# 06_RTL8711.net
KiCad netlist of a schematic drawn in Altium Designer
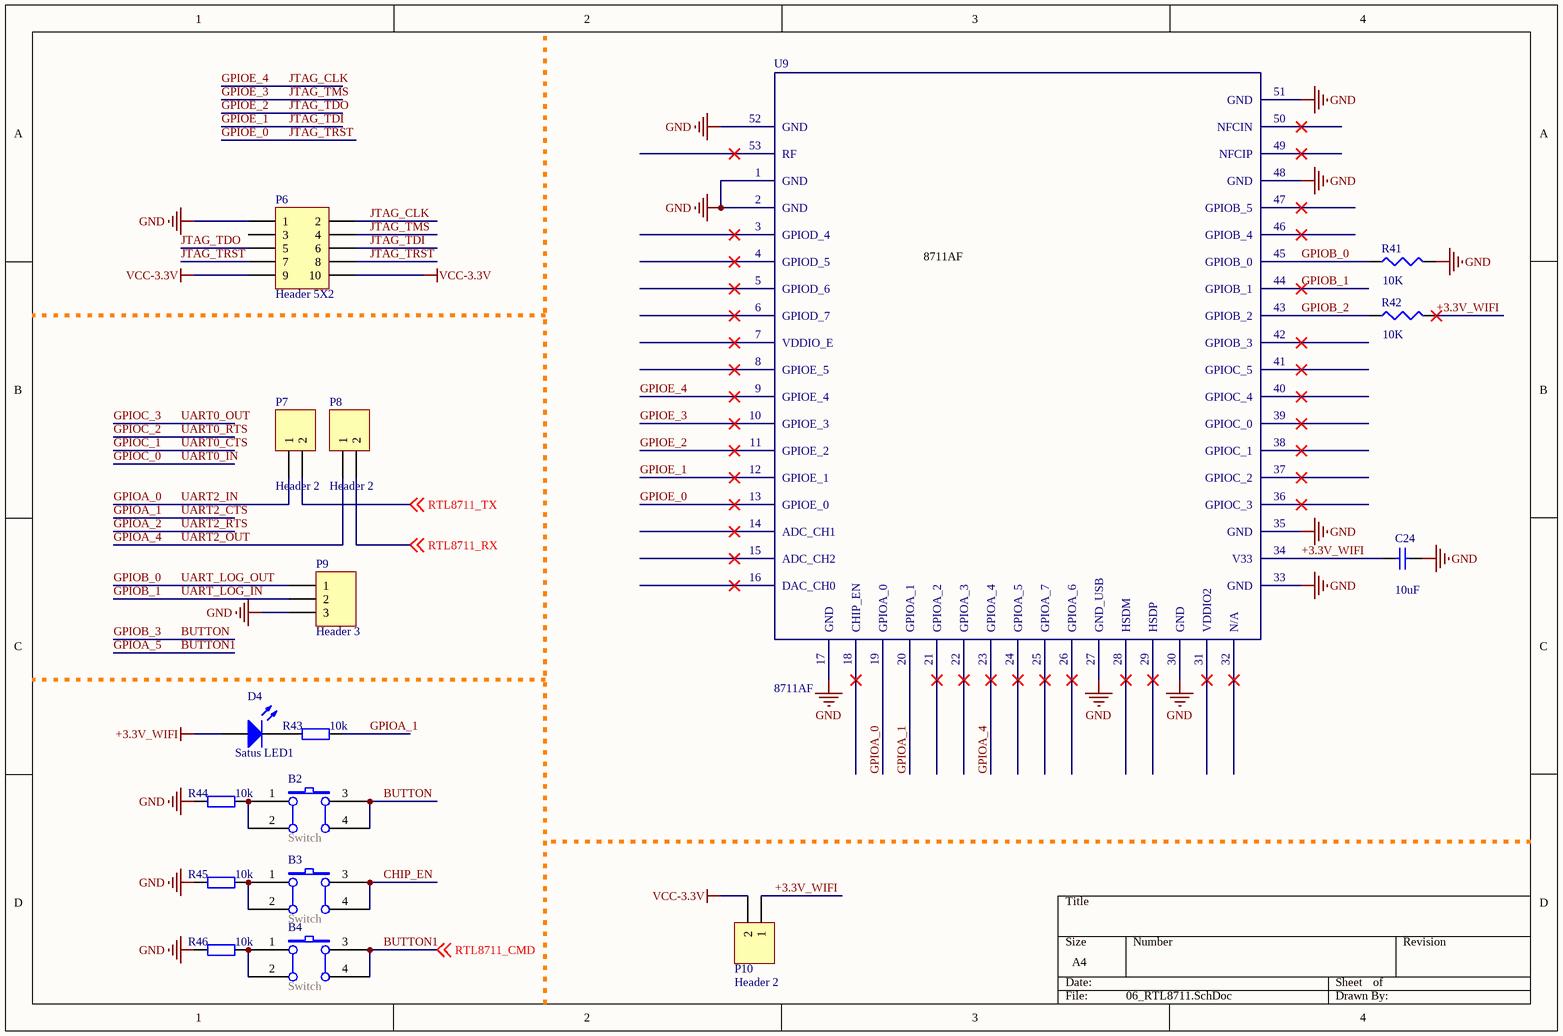
[diagram p0: 06_RTL8711.SchDoc]

(export (version "E")
  (design (tool "Eeschema 10.0.6"))
  (components
    (comp (ref "B2")
      (value "Switch")
      (footprint "Miscellaneous Modules:SWITCH-0.65/0.45")
      (description "Tactile Switch")
      (libsource (lib "Miscellaneous Modules") (part "Switch"))
    )
    (comp (ref "B3")
      (value "Switch")
      (footprint "Miscellaneous Modules:SWITCH-0.65/0.45")
      (description "Tactile Switch")
      (libsource (lib "Miscellaneous Modules") (part "Switch"))
    )
    (comp (ref "B4")
      (value "Switch")
      (footprint "Miscellaneous Modules:SWITCH-0.65/0.45")
      (description "Tactile Switch")
      (libsource (lib "Miscellaneous Modules") (part "Switch"))
    )
    (comp (ref "C24")
      (value "10uF")
      (footprint "RB2.5-6.3")
      (description "Capacitor (Semiconductor SIM Model)")
      (fields (field (name "PUBLISHER") "Altium Limited"))
      (libsource (lib "Miscellaneous Devices") (part "Cap Semi"))
    )
    (comp (ref "D4")
      (value "Satus LED1")
      (footprint "LED-R3.0")
      (description "Typical RED GaAs LED")
      (fields (field (name "PUBLISHER") "Altium Limited"))
      (libsource (lib "Miscellaneous Devices") (part "LED1"))
    )
    (comp (ref "P6")
      (value "Header 5X2")
      (footprint "HDR2X5")
      (description "Header, 5-Pin, Dual row")
      (fields (field (name "PUBLISHER") "Altium Limited"))
      (libsource (lib "Miscellaneous Connectors") (part "Header 5X2"))
    )
    (comp (ref "P7")
      (value "Header 2")
      (footprint "HDR1X2")
      (description "Header, 2-Pin")
      (fields (field (name "PUBLISHER") "Altium Limited"))
      (libsource (lib "Miscellaneous Connectors") (part "Header 2"))
    )
    (comp (ref "P8")
      (value "Header 2")
      (footprint "HDR1X2")
      (description "Header, 2-Pin")
      (fields (field (name "PUBLISHER") "Altium Limited"))
      (libsource (lib "Miscellaneous Connectors") (part "Header 2"))
    )
    (comp (ref "P9")
      (value "Header 3")
      (footprint "HDR1X3")
      (description "Header, 3-Pin")
      (fields (field (name "PUBLISHER") "Altium Limited"))
      (libsource (lib "Miscellaneous Connectors") (part "Header 3"))
    )
    (comp (ref "P10")
      (value "Header 2")
      (footprint "HDR1X2")
      (description "Header, 2-Pin")
      (fields (field (name "PUBLISHER") "Altium Limited"))
      (libsource (lib "") (part "Header 2_1"))
    )
    (comp (ref "R41")
      (value "10K")
      (footprint "AXIAL-0.3")
      (description "Resistor")
      (fields (field (name "PUBLISHER") "Altium Limited"))
      (libsource (lib "Miscellaneous Devices") (part "Res3"))
    )
    (comp (ref "R42")
      (value "10K")
      (footprint "AXIAL-0.3")
      (description "Resistor")
      (fields (field (name "PUBLISHER") "Altium Limited"))
      (libsource (lib "Miscellaneous Devices") (part "Res3"))
    )
    (comp (ref "R43")
      (value "10k")
      (footprint "AXIAL-0.3")
      (description "贴片电阻")
      (fields (field (name "PUBLISHER") "Altium Limited"))
      (libsource (lib "fszhang") (part "Res1"))
    )
    (comp (ref "R44")
      (value "10k")
      (footprint "AXIAL-0.3")
      (description "贴片电阻")
      (fields (field (name "PUBLISHER") "Altium Limited"))
      (libsource (lib "fszhang") (part "Res1"))
    )
    (comp (ref "R45")
      (value "10k")
      (footprint "AXIAL-0.3")
      (description "贴片电阻")
      (fields (field (name "PUBLISHER") "Altium Limited"))
      (libsource (lib "fszhang") (part "Res1"))
    )
    (comp (ref "R46")
      (value "10k")
      (footprint "AXIAL-0.3")
      (description "贴片电阻")
      (fields (field (name "PUBLISHER") "Altium Limited"))
      (libsource (lib "fszhang") (part "Res1"))
    )
    (comp (ref "U9")
      (value "8711AF")
      (footprint "53PIN-MODULE-PLATFORM -2")
      (libsource (lib "RTL-8711AF") (part "8711AF"))
    )
  )
  (nets
    (net (code "1") (name "+3.3V_WIFI") (class "Default")
      (node (ref "C24") (pin "1") (pinfunction "1_1") (pintype "passive"))
      (node (ref "D4") (pin "1") (pinfunction "A_1") (pintype "passive"))
      (node (ref "P10") (pin "1") (pinfunction "1_1") (pintype "passive"))
      (node (ref "R42") (pin "2") (pinfunction "2_2") (pintype "passive"))
      (node (ref "U9") (pin "34") (pinfunction "V33_34") (pintype "passive"))
    )
    (net (code "2") (name "/BUTTON") (class "Default")
      (node (ref "B2") (pin "3") (pinfunction "B1_3") (pintype "passive"))
      (node (ref "B2") (pin "4") (pinfunction "A1_4") (pintype "passive"))
    )
    (net (code "3") (name "/CHIP_EN") (class "Default")
      (node (ref "B3") (pin "3") (pinfunction "B1_3") (pintype "passive"))
      (node (ref "B3") (pin "4") (pinfunction "A1_4") (pintype "passive"))
    )
    (net (code "4") (name "/GPIOA_0") (class "Default")
      (node (ref "P7") (pin "1") (pinfunction "1_1") (pintype "passive"))
      (node (ref "U9") (pin "19") (pinfunction "GPIOA_0_19") (pintype "passive"))
    )
    (net (code "5") (name "/GPIOA_1") (class "Default")
      (node (ref "R43") (pin "2") (pinfunction "2_2") (pintype "passive"))
      (node (ref "U9") (pin "20") (pinfunction "GPIOA_1_20") (pintype "passive"))
    )
    (net (code "7") (name "/GPIOA_4") (class "Default")
      (node (ref "P8") (pin "1") (pinfunction "1_1") (pintype "passive"))
      (node (ref "U9") (pin "23") (pinfunction "GPIOA_4_23") (pintype "passive"))
    )
    (net (code "8") (name "/GPIOB_0") (class "Default")
      (node (ref "P9") (pin "1") (pinfunction "1_1") (pintype "passive"))
      (node (ref "R41") (pin "1") (pinfunction "1_1") (pintype "passive"))
      (node (ref "U9") (pin "45") (pinfunction "GPIOB_0_45") (pintype "passive"))
    )
    (net (code "9") (name "/GPIOB_1") (class "Default")
      (node (ref "P9") (pin "2") (pinfunction "2_2") (pintype "passive"))
      (node (ref "U9") (pin "44") (pinfunction "GPIOB_1_44") (pintype "passive"))
    )
    (net (code "10") (name "/GPIOB_2") (class "Default")
      (node (ref "R42") (pin "1") (pinfunction "1_1") (pintype "passive"))
      (node (ref "U9") (pin "43") (pinfunction "GPIOB_2_43") (pintype "passive"))
    )
    (net (code "15") (name "/GPIOE_0") (class "Default")
      (node (ref "P6") (pin "7") (pinfunction "7_7") (pintype "passive"))
      (node (ref "P6") (pin "8") (pinfunction "8_8") (pintype "passive"))
      (node (ref "U9") (pin "13") (pinfunction "GPIOE_0_13") (pintype "passive"))
    )
    (net (code "16") (name "/GPIOE_1") (class "Default")
      (node (ref "P6") (pin "6") (pinfunction "6_6") (pintype "passive"))
      (node (ref "U9") (pin "12") (pinfunction "GPIOE_1_12") (pintype "passive"))
    )
    (net (code "17") (name "/GPIOE_2") (class "Default")
      (node (ref "P6") (pin "5") (pinfunction "5_5") (pintype "passive"))
      (node (ref "U9") (pin "11") (pinfunction "GPIOE_2_11") (pintype "passive"))
    )
    (net (code "18") (name "/GPIOE_3") (class "Default")
      (node (ref "P6") (pin "4") (pinfunction "4_4") (pintype "passive"))
      (node (ref "U9") (pin "10") (pinfunction "GPIOE_3_10") (pintype "passive"))
    )
    (net (code "19") (name "/GPIOE_4") (class "Default")
      (node (ref "P6") (pin "2") (pinfunction "2_2") (pintype "passive"))
      (node (ref "U9") (pin "9") (pinfunction "GPIOE_4_9") (pintype "passive"))
    )
    (net (code "20") (name "GND") (class "Default")
      (node (ref "C24") (pin "2") (pinfunction "2_2") (pintype "passive"))
      (node (ref "P6") (pin "1") (pinfunction "1_1") (pintype "passive"))
      (node (ref "P9") (pin "3") (pinfunction "3_3") (pintype "passive"))
      (node (ref "R41") (pin "2") (pinfunction "2_2") (pintype "passive"))
      (node (ref "R44") (pin "1") (pinfunction "1_1") (pintype "passive"))
      (node (ref "R45") (pin "1") (pinfunction "1_1") (pintype "passive"))
      (node (ref "R46") (pin "1") (pinfunction "1_1") (pintype "passive"))
      (node (ref "U9") (pin "1") (pinfunction "GND_1") (pintype "passive"))
      (node (ref "U9") (pin "17") (pinfunction "GND_17") (pintype "passive"))
      (node (ref "U9") (pin "2") (pinfunction "GND_2") (pintype "passive"))
      (node (ref "U9") (pin "27") (pinfunction "GND_USB_27") (pintype "passive"))
      (node (ref "U9") (pin "30") (pinfunction "GND_30") (pintype "passive"))
      (node (ref "U9") (pin "33") (pinfunction "GND_33") (pintype "passive"))
      (node (ref "U9") (pin "35") (pinfunction "GND_35") (pintype "passive"))
      (node (ref "U9") (pin "48") (pinfunction "GND_48") (pintype "passive"))
      (node (ref "U9") (pin "51") (pinfunction "GND_51") (pintype "passive"))
      (node (ref "U9") (pin "52") (pinfunction "GND_52") (pintype "passive"))
    )
    (net (code "21") (name "Net-(B2-A0)") (class "Default")
      (node (ref "B2") (pin "1") (pinfunction "A0_1") (pintype "passive"))
      (node (ref "B2") (pin "2") (pinfunction "B0_2") (pintype "passive"))
      (node (ref "R44") (pin "2") (pinfunction "2_2") (pintype "passive"))
    )
    (net (code "22") (name "Net-(B3-A0)") (class "Default")
      (node (ref "B3") (pin "1") (pinfunction "A0_1") (pintype "passive"))
      (node (ref "B3") (pin "2") (pinfunction "B0_2") (pintype "passive"))
      (node (ref "R45") (pin "2") (pinfunction "2_2") (pintype "passive"))
    )
    (net (code "23") (name "Net-(B4-A0)") (class "Default")
      (node (ref "B4") (pin "1") (pinfunction "A0_1") (pintype "passive"))
      (node (ref "B4") (pin "2") (pinfunction "B0_2") (pintype "passive"))
      (node (ref "R46") (pin "2") (pinfunction "2_2") (pintype "passive"))
    )
    (net (code "24") (name "Net-(D4-K)") (class "Default")
      (node (ref "D4") (pin "2") (pinfunction "K_2") (pintype "passive"))
      (node (ref "R43") (pin "1") (pinfunction "1_1") (pintype "passive"))
    )
    (net (code "25") (name "RTL8711_CMD") (class "Default")
      (node (ref "B4") (pin "3") (pinfunction "B1_3") (pintype "passive"))
      (node (ref "B4") (pin "4") (pinfunction "A1_4") (pintype "passive"))
    )
    (net (code "26") (name "RTL8711_RX") (class "Default")
      (node (ref "P8") (pin "2") (pinfunction "2_2") (pintype "passive"))
    )
    (net (code "27") (name "RTL8711_TX") (class "Default")
      (node (ref "P7") (pin "2") (pinfunction "2_2") (pintype "passive"))
    )
    (net (code "28") (name "VCC-3.3V") (class "Default")
      (node (ref "P10") (pin "2") (pinfunction "2_2") (pintype "passive"))
      (node (ref "P6") (pin "10") (pinfunction "10_10") (pintype "passive"))
      (node (ref "P6") (pin "9") (pinfunction "9_9") (pintype "passive"))
    )
    (net (code "29") (name "unconnected-(P6-Pad3)") (class "Default")
      (node (ref "P6") (pin "3") (pinfunction "3_3") (pintype "passive"))
    )
    (net (code "30") (name "unconnected-(U9-ADC_CH1-Pad14)") (class "Default")
      (node (ref "U9") (pin "14") (pinfunction "ADC_CH1_14") (pintype "passive+no_connect"))
    )
    (net (code "31") (name "unconnected-(U9-ADC_CH2-Pad15)") (class "Default")
      (node (ref "U9") (pin "15") (pinfunction "ADC_CH2_15") (pintype "passive+no_connect"))
    )
    (net (code "32") (name "unconnected-(U9-CHIP_EN-Pad18)") (class "Default")
      (node (ref "U9") (pin "18") (pinfunction "CHIP_EN_18") (pintype "passive+no_connect"))
    )
    (net (code "33") (name "unconnected-(U9-DAC_CH0-Pad16)") (class "Default")
      (node (ref "U9") (pin "16") (pinfunction "DAC_CH0_16") (pintype "passive+no_connect"))
    )
    (net (code "34") (name "unconnected-(U9-GPIOA_2-Pad21)") (class "Default")
      (node (ref "U9") (pin "21") (pinfunction "GPIOA_2_21") (pintype "passive+no_connect"))
    )
    (net (code "35") (name "unconnected-(U9-GPIOA_3-Pad22)") (class "Default")
      (node (ref "U9") (pin "22") (pinfunction "GPIOA_3_22") (pintype "passive+no_connect"))
    )
    (net (code "36") (name "unconnected-(U9-GPIOA_5-Pad24)") (class "Default")
      (node (ref "U9") (pin "24") (pinfunction "GPIOA_5_24") (pintype "passive+no_connect"))
    )
    (net (code "37") (name "unconnected-(U9-GPIOA_6-Pad26)") (class "Default")
      (node (ref "U9") (pin "26") (pinfunction "GPIOA_6_26") (pintype "passive+no_connect"))
    )
    (net (code "38") (name "unconnected-(U9-GPIOA_7-Pad25)") (class "Default")
      (node (ref "U9") (pin "25") (pinfunction "GPIOA_7_25") (pintype "passive+no_connect"))
    )
    (net (code "39") (name "unconnected-(U9-GPIOB_3-Pad42)") (class "Default")
      (node (ref "U9") (pin "42") (pinfunction "GPIOB_3_42") (pintype "passive+no_connect"))
    )
    (net (code "40") (name "unconnected-(U9-GPIOB_4-Pad46)") (class "Default")
      (node (ref "U9") (pin "46") (pinfunction "GPIOB_4_46") (pintype "passive+no_connect"))
    )
    (net (code "41") (name "unconnected-(U9-GPIOB_5-Pad47)") (class "Default")
      (node (ref "U9") (pin "47") (pinfunction "GPIOB_5_47") (pintype "passive+no_connect"))
    )
    (net (code "42") (name "unconnected-(U9-GPIOC_0-Pad39)") (class "Default")
      (node (ref "U9") (pin "39") (pinfunction "GPIOC_0_39") (pintype "passive+no_connect"))
    )
    (net (code "43") (name "unconnected-(U9-GPIOC_1-Pad38)") (class "Default")
      (node (ref "U9") (pin "38") (pinfunction "GPIOC_1_38") (pintype "passive+no_connect"))
    )
    (net (code "44") (name "unconnected-(U9-GPIOC_2-Pad37)") (class "Default")
      (node (ref "U9") (pin "37") (pinfunction "GPIOC_2_37") (pintype "passive+no_connect"))
    )
    (net (code "45") (name "unconnected-(U9-GPIOC_3-Pad36)") (class "Default")
      (node (ref "U9") (pin "36") (pinfunction "GPIOC_3_36") (pintype "passive+no_connect"))
    )
    (net (code "46") (name "unconnected-(U9-GPIOC_4-Pad40)") (class "Default")
      (node (ref "U9") (pin "40") (pinfunction "GPIOC_4_40") (pintype "passive+no_connect"))
    )
    (net (code "47") (name "unconnected-(U9-GPIOC_5-Pad41)") (class "Default")
      (node (ref "U9") (pin "41") (pinfunction "GPIOC_5_41") (pintype "passive+no_connect"))
    )
    (net (code "48") (name "unconnected-(U9-GPIOD_4-Pad3)") (class "Default")
      (node (ref "U9") (pin "3") (pinfunction "GPIOD_4_3") (pintype "passive+no_connect"))
    )
    (net (code "49") (name "unconnected-(U9-GPIOD_5-Pad4)") (class "Default")
      (node (ref "U9") (pin "4") (pinfunction "GPIOD_5_4") (pintype "passive+no_connect"))
    )
    (net (code "50") (name "unconnected-(U9-GPIOD_6-Pad5)") (class "Default")
      (node (ref "U9") (pin "5") (pinfunction "GPIOD_6_5") (pintype "passive+no_connect"))
    )
    (net (code "51") (name "unconnected-(U9-GPIOD_7-Pad6)") (class "Default")
      (node (ref "U9") (pin "6") (pinfunction "GPIOD_7_6") (pintype "passive+no_connect"))
    )
    (net (code "52") (name "unconnected-(U9-GPIOE_5-Pad8)") (class "Default")
      (node (ref "U9") (pin "8") (pinfunction "GPIOE_5_8") (pintype "passive+no_connect"))
    )
    (net (code "53") (name "unconnected-(U9-HSDM-Pad28)") (class "Default")
      (node (ref "U9") (pin "28") (pinfunction "HSDM_28") (pintype "passive+no_connect"))
    )
    (net (code "54") (name "unconnected-(U9-HSDP-Pad29)") (class "Default")
      (node (ref "U9") (pin "29") (pinfunction "HSDP_29") (pintype "passive+no_connect"))
    )
    (net (code "55") (name "unconnected-(U9-NFCIN-Pad50)") (class "Default")
      (node (ref "U9") (pin "50") (pinfunction "NFCIN_50") (pintype "passive+no_connect"))
    )
    (net (code "56") (name "unconnected-(U9-NFCIP-Pad49)") (class "Default")
      (node (ref "U9") (pin "49") (pinfunction "NFCIP_49") (pintype "passive+no_connect"))
    )
    (net (code "57") (name "unconnected-(U9-N{slash}A-Pad32)") (class "Default")
      (node (ref "U9") (pin "32") (pinfunction "N/A_32") (pintype "passive+no_connect"))
    )
    (net (code "58") (name "unconnected-(U9-RF-Pad53)") (class "Default")
      (node (ref "U9") (pin "53") (pinfunction "RF_53") (pintype "passive+no_connect"))
    )
    (net (code "59") (name "unconnected-(U9-VDDIO2-Pad31)") (class "Default")
      (node (ref "U9") (pin "31") (pinfunction "VDDIO2_31") (pintype "passive+no_connect"))
    )
    (net (code "60") (name "unconnected-(U9-VDDIO_E-Pad7)") (class "Default")
      (node (ref "U9") (pin "7") (pinfunction "VDDIO_E_7") (pintype "passive+no_connect"))
    )
  )
)
